# ir-kh.net
KiCad netlist of a schematic drawn in Altium Designer
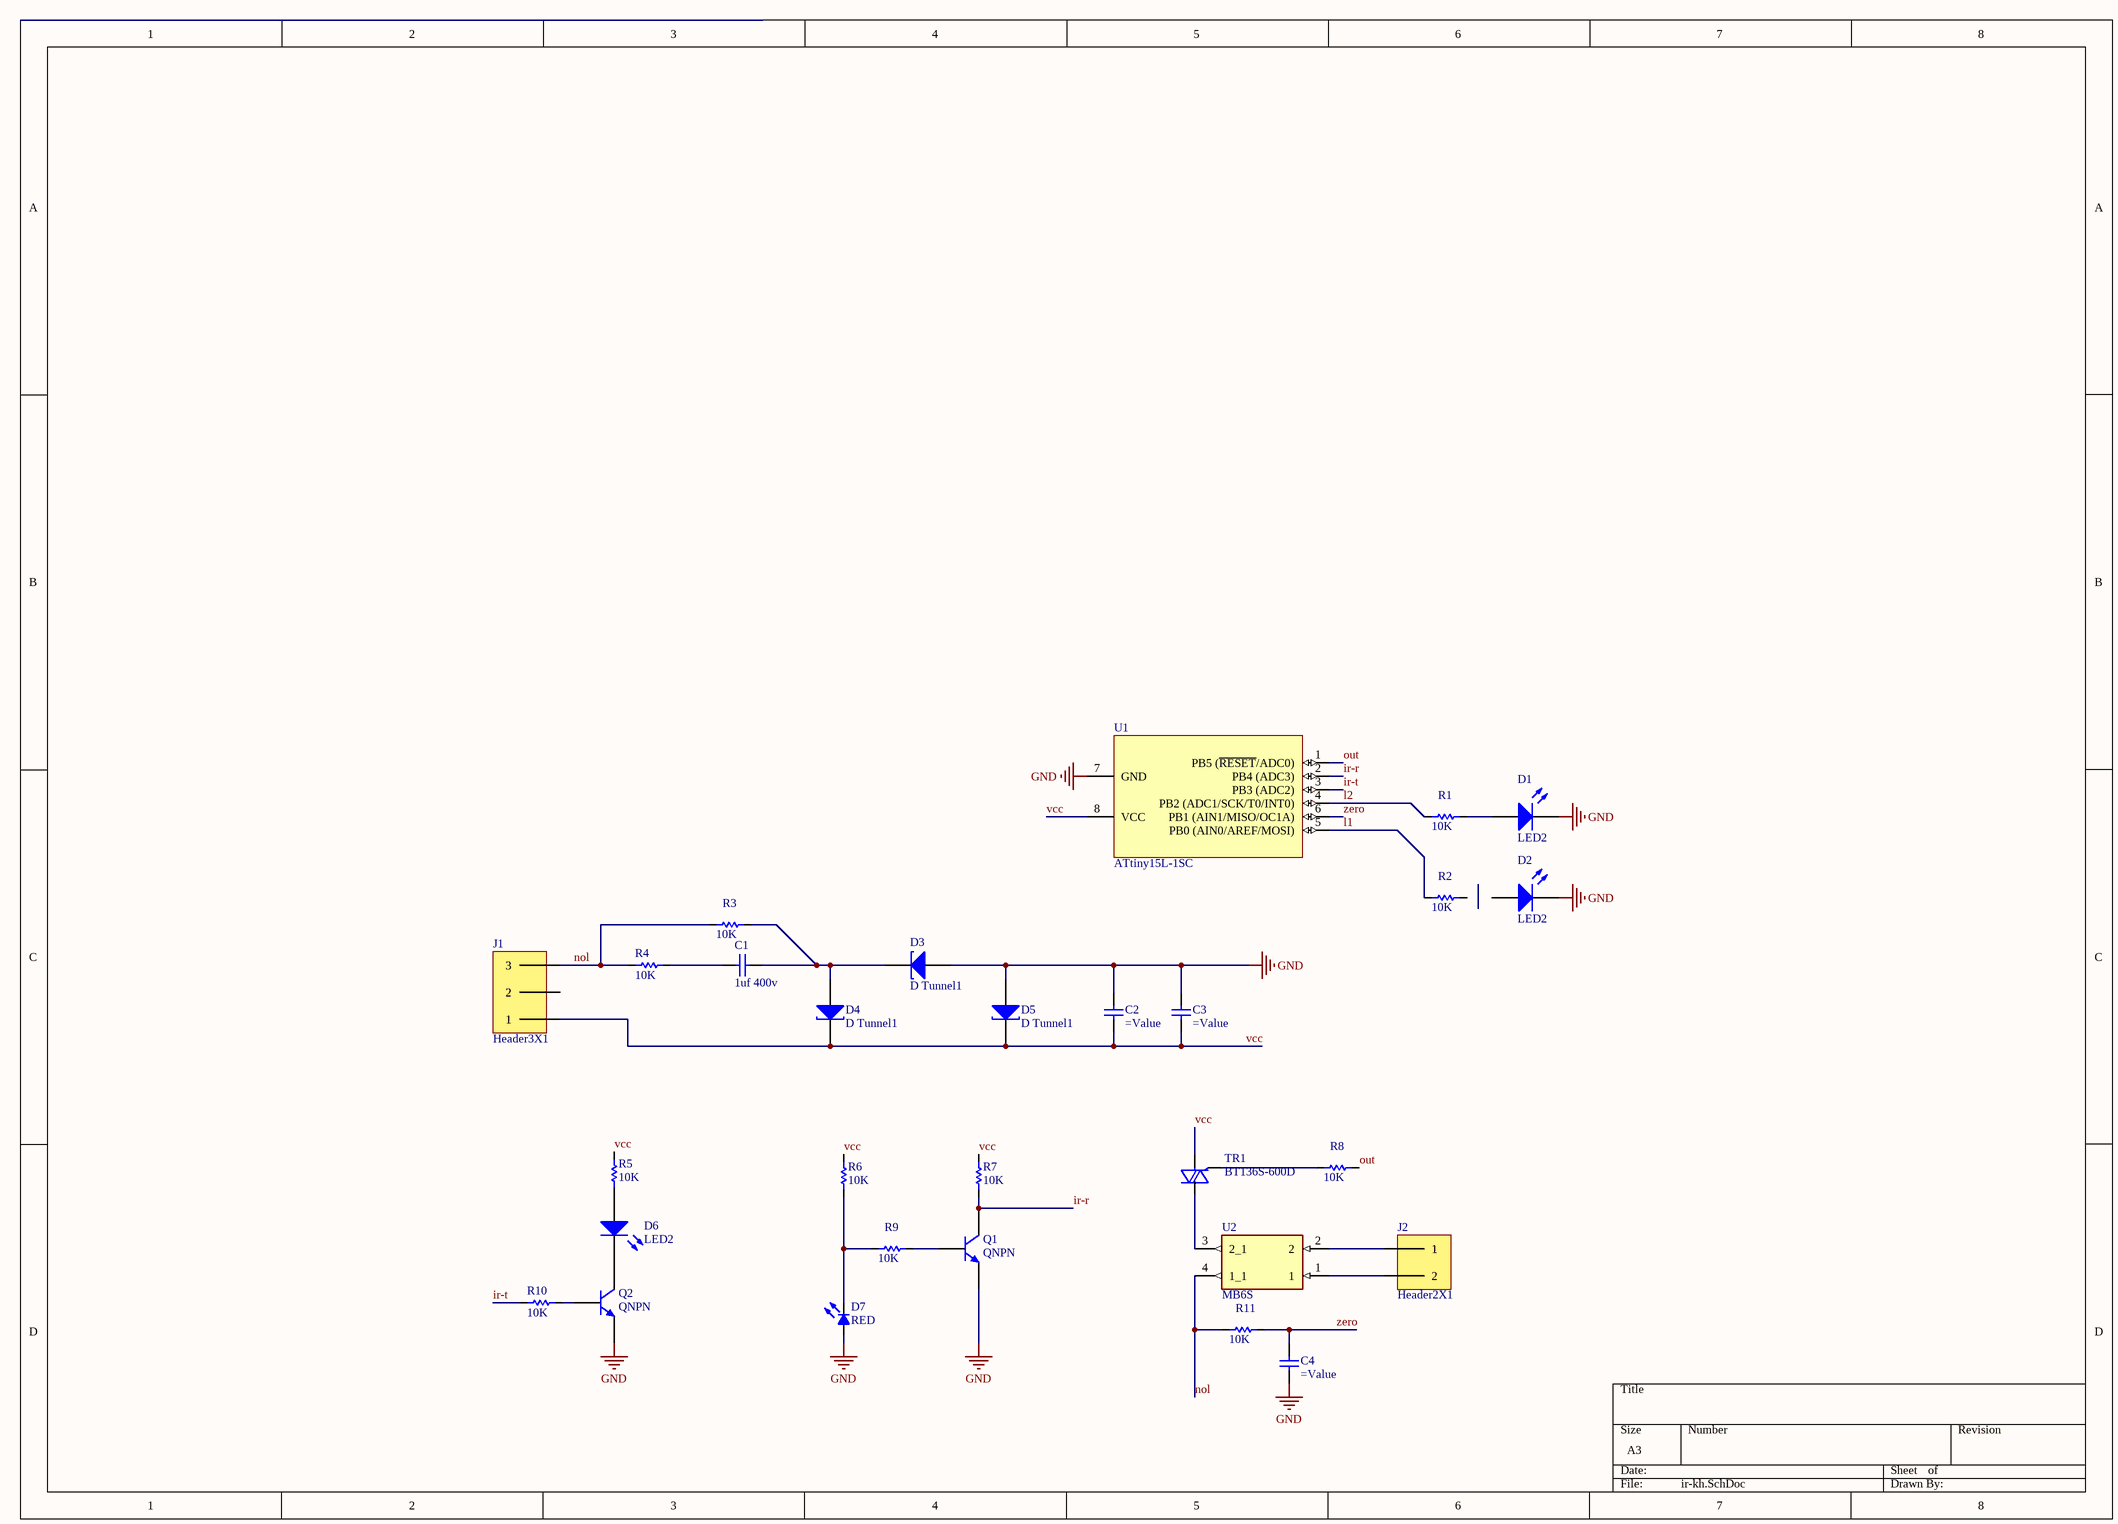
[diagram p0: ir-kh.SchDoc]

(export (version "E")
  (design (tool "Eeschema 10.0.6"))
  (components
    (comp (ref "C1")
      (value "1uf 400v")
      (footprint "1uf 400v")
      (description "Capacitor 24*9mm")
      (fields (field (name "DESIGNER") "Seyed Mohsen Ghasemain"))
      (libsource (lib "PicPars.com_usefully_Library") (part "1uf 400v"))
    )
    (comp (ref "C2")
      (value "~")
      (footprint "CAP 1206")
      (description "Capacitor")
      (libsource (lib "AltiumLib1") (part "Capacitor"))
    )
    (comp (ref "C3")
      (value "~")
      (footprint "CAP 1206")
      (description "Capacitor")
      (libsource (lib "AltiumLib1") (part "Capacitor"))
    )
    (comp (ref "C4")
      (value "~")
      (footprint "CAP 1206")
      (description "Capacitor")
      (libsource (lib "AltiumLib1") (part "Capacitor"))
    )
    (comp (ref "D1")
      (value "LED2")
      (footprint "3.2X1.6X1.1")
      (description "Typical RED, GREEN, YELLOW, AMBER GaAs LED")
      (fields (field (name "PUBLISHER") "Altium Limited"))
      (libsource (lib "Miscellaneous Devices") (part "LED2"))
    )
    (comp (ref "D2")
      (value "LED2")
      (footprint "3.2X1.6X1.1")
      (description "Typical RED, GREEN, YELLOW, AMBER GaAs LED")
      (fields (field (name "PUBLISHER") "Altium Limited"))
      (libsource (lib "Miscellaneous Devices") (part "LED2"))
    )
    (comp (ref "D3")
      (value "D Tunnel1")
      (footprint "3.2X1.6X1.1")
      (description "Tunnel Diode - RLC Model")
      (fields (field (name "PUBLISHER") "Altium Limited"))
      (libsource (lib "Miscellaneous Devices") (part "D Tunnel1"))
    )
    (comp (ref "D4")
      (value "D Tunnel1")
      (footprint "3.2X1.6X1.1")
      (description "Tunnel Diode - RLC Model")
      (fields (field (name "PUBLISHER") "Altium Limited"))
      (libsource (lib "Miscellaneous Devices") (part "D Tunnel1"))
    )
    (comp (ref "D5")
      (value "D Tunnel1")
      (footprint "3.2X1.6X1.1")
      (description "Tunnel Diode - RLC Model")
      (fields (field (name "PUBLISHER") "Altium Limited"))
      (libsource (lib "Miscellaneous Devices") (part "D Tunnel1"))
    )
    (comp (ref "D6")
      (value "LED2")
      (footprint "3.2X1.6X1.1")
      (description "Typical RED, GREEN, YELLOW, AMBER GaAs LED")
      (fields (field (name "PUBLISHER") "Altium Limited"))
      (libsource (lib "Miscellaneous Devices") (part "LED2"))
    )
    (comp (ref "D7")
      (value "MODEL")
      (footprint "LED-5mm")
      (description "Typical LED")
      (fields (field (name "COLOR") "RED"))
      (libsource (lib "AltiumLib1") (part "LED 5mm"))
    )
    (comp (ref "J1")
      (value "Header3X1")
      (footprint "HEADER 3X1")
      (libsource (lib "AltiumLib1") (part "Header3X1"))
    )
    (comp (ref "J2")
      (value "Header2X1")
      (footprint "Header 2X1")
      (libsource (lib "AltiumLib1") (part "Header2X1"))
    )
    (comp (ref "Q1")
      (value "QNPN")
      (footprint "SOT-23B_L")
      (description "NPN Bipolar Transistor")
      (fields (field (name "PUBLISHER") "Altium Limited"))
      (libsource (lib "Miscellaneous Devices") (part "QNPN"))
    )
    (comp (ref "Q2")
      (value "QNPN")
      (footprint "SOT-23B_L")
      (description "NPN Bipolar Transistor")
      (fields (field (name "PUBLISHER") "Altium Limited"))
      (libsource (lib "Miscellaneous Devices") (part "QNPN"))
    )
    (comp (ref "R1")
      (value "10K")
      (footprint "RES 1206 (3216X08L)")
      (description "Resistor")
      (fields (field (name "TOLERANCE") "5%") (field (name "POWER") "1/4 W"))
      (libsource (lib "AltiumLib1") (part "Resistor"))
    )
    (comp (ref "R2")
      (value "10K")
      (footprint "RES 1206 (3216X08L)")
      (description "Resistor")
      (fields (field (name "TOLERANCE") "5%") (field (name "POWER") "1/4 W"))
      (libsource (lib "AltiumLib1") (part "Resistor"))
    )
    (comp (ref "R3")
      (value "10K")
      (footprint "RES 1206 (3216X08L)")
      (description "Resistor")
      (fields (field (name "TOLERANCE") "5%") (field (name "POWER") "1/4 W"))
      (libsource (lib "AltiumLib1") (part "Resistor"))
    )
    (comp (ref "R4")
      (value "10K")
      (footprint "Res-(2/1)")
      (description "Resistor")
      (fields (field (name "TOLERANCE") "5%") (field (name "POWER") "1/4 W"))
      (libsource (lib "AltiumLib1") (part "Resistor"))
    )
    (comp (ref "R5")
      (value "10K")
      (footprint "RES 1206 (3216X08L)")
      (description "Resistor")
      (fields (field (name "TOLERANCE") "5%") (field (name "POWER") "1/4 W"))
      (libsource (lib "AltiumLib1") (part "Resistor"))
    )
    (comp (ref "R6")
      (value "10K")
      (footprint "RES 1206 (3216X08L)")
      (description "Resistor")
      (fields (field (name "TOLERANCE") "5%") (field (name "POWER") "1/4 W"))
      (libsource (lib "AltiumLib1") (part "Resistor"))
    )
    (comp (ref "R7")
      (value "10K")
      (footprint "RES 1206 (3216X08L)")
      (description "Resistor")
      (fields (field (name "TOLERANCE") "5%") (field (name "POWER") "1/4 W"))
      (libsource (lib "AltiumLib1") (part "Resistor"))
    )
    (comp (ref "R8")
      (value "10K")
      (footprint "RES 1206 (3216X08L)")
      (description "Resistor")
      (fields (field (name "TOLERANCE") "5%") (field (name "POWER") "1/4 W"))
      (libsource (lib "AltiumLib1") (part "Resistor"))
    )
    (comp (ref "R9")
      (value "10K")
      (footprint "RES 1206 (3216X08L)")
      (description "Resistor")
      (fields (field (name "TOLERANCE") "5%") (field (name "POWER") "1/4 W"))
      (libsource (lib "AltiumLib1") (part "Resistor"))
    )
    (comp (ref "R10")
      (value "10K")
      (footprint "RES 1206 (3216X08L)")
      (description "Resistor")
      (fields (field (name "TOLERANCE") "5%") (field (name "POWER") "1/4 W"))
      (libsource (lib "AltiumLib1") (part "Resistor"))
    )
    (comp (ref "R11")
      (value "10K")
      (footprint "RES 1206 (3216X08L)")
      (description "Resistor")
      (fields (field (name "TOLERANCE") "5%") (field (name "POWER") "1/4 W"))
      (libsource (lib "AltiumLib1") (part "Resistor"))
    )
    (comp (ref "TR1")
      (value "BT136S-600D")
      (footprint "SOT428")
      (description "TRIAC 600V 27A 3-Pin(2+Tab) DPAK")
      (fields (field (name "MF") "WeEn Semiconductor(Hong Kong)Co.,Limited"))
      (libsource (lib "BT136S-600D") (part "BT136S-600D"))
    )
    (comp (ref "U1")
      (value "ATtiny15L-1SC")
      (footprint "8S2_N")
      (description "8-Bit AVR Microcontroller with 1K Byte of Flash Memory")
      (fields (field (name "PUBLISHER") "Altium Limited"))
      (libsource (lib "Atmel Microcontroller 8-Bit AVR") (part "ATtiny15L-1SC"))
    )
    (comp (ref "U2")
      (value "MB6S")
      (footprint "SOIC245P670X270-4N")
      (description "Bridge Rectifier Single Phase Standard 600V Surface Mount 4-SOIC")
      (fields (field (name "MF") "ON Semiconductor") (field (name "DIGI-KEY_PART_NUMBER") "MB6SCT-ND"))
      (libsource (lib "MB6S") (part "MB6S"))
    )
  )
  (nets
    (net (code "1") (name "/ir-r") (class "Default")
      (node (ref "Q1") (pin "1") (pinfunction "C_1") (pintype "passive"))
      (node (ref "R7") (pin "2") (pinfunction "2_2") (pintype "passive"))
      (node (ref "U1") (pin "2") (pinfunction "PB4_(ADC3)_2") (pintype "bidirectional"))
    )
    (net (code "2") (name "/ir-t") (class "Default")
      (node (ref "R10") (pin "1") (pinfunction "1_1") (pintype "passive"))
      (node (ref "U1") (pin "3") (pinfunction "PB3_(ADC2)_3") (pintype "bidirectional"))
    )
    (net (code "3") (name "/l1") (class "Default")
      (node (ref "R2") (pin "1") (pinfunction "1_1") (pintype "passive"))
      (node (ref "U1") (pin "5") (pinfunction "PB0_(AIN0/AREF/MOSI)_5") (pintype "bidirectional"))
    )
    (net (code "4") (name "/l2") (class "Default")
      (node (ref "R1") (pin "1") (pinfunction "1_1") (pintype "passive"))
      (node (ref "U1") (pin "4") (pinfunction "PB2_(ADC1/SCK/T0/INT0)_4") (pintype "bidirectional"))
    )
    (net (code "5") (name "/nol") (class "Default")
      (node (ref "J1") (pin "3") (pinfunction "3_3") (pintype "passive"))
      (node (ref "R11") (pin "1") (pinfunction "1_1") (pintype "passive"))
      (node (ref "R3") (pin "1") (pinfunction "1_1") (pintype "passive"))
      (node (ref "R4") (pin "1") (pinfunction "1_1") (pintype "passive"))
      (node (ref "U2") (pin "4") (pinfunction "1_1_4") (pintype "output"))
    )
    (net (code "6") (name "/out") (class "Default")
      (node (ref "R8") (pin "2") (pinfunction "2_2") (pintype "passive"))
      (node (ref "U1") (pin "1") (pinfunction "PB5_(~{RESET}/ADC0)_1") (pintype "bidirectional"))
    )
    (net (code "7") (name "/vcc") (class "Default")
      (node (ref "C2") (pin "1") (pinfunction "+_1") (pintype "passive"))
      (node (ref "C3") (pin "1") (pinfunction "+_1") (pintype "passive"))
      (node (ref "D4") (pin "2") (pinfunction "K_2") (pintype "passive"))
      (node (ref "D5") (pin "2") (pinfunction "K_2") (pintype "passive"))
      (node (ref "J1") (pin "1") (pinfunction "1_1") (pintype "passive"))
      (node (ref "R5") (pin "2") (pinfunction "2_2") (pintype "passive"))
      (node (ref "R6") (pin "1") (pinfunction "1_1") (pintype "passive"))
      (node (ref "R7") (pin "1") (pinfunction "1_1") (pintype "passive"))
      (node (ref "TR1") (pin "1") (pinfunction "A1_1") (pintype "passive"))
      (node (ref "U1") (pin "8") (pinfunction "VCC_8") (pintype "power_in"))
    )
    (net (code "8") (name "/zero") (class "Default")
      (node (ref "C4") (pin "2") (pinfunction "-_2") (pintype "passive"))
      (node (ref "R11") (pin "2") (pinfunction "2_2") (pintype "passive"))
      (node (ref "U1") (pin "6") (pinfunction "PB1_(AIN1/MISO/OC1A)_6") (pintype "bidirectional"))
    )
    (net (code "9") (name "GND") (class "Default")
      (node (ref "C2") (pin "2") (pinfunction "-_2") (pintype "passive"))
      (node (ref "C3") (pin "2") (pinfunction "-_2") (pintype "passive"))
      (node (ref "C4") (pin "1") (pinfunction "+_1") (pintype "passive"))
      (node (ref "D1") (pin "2") (pinfunction "K_2") (pintype "passive"))
      (node (ref "D2") (pin "2") (pinfunction "K_2") (pintype "passive"))
      (node (ref "D3") (pin "1") (pinfunction "A_1") (pintype "passive"))
      (node (ref "D5") (pin "1") (pinfunction "A_1") (pintype "passive"))
      (node (ref "D7") (pin "1") (pinfunction "A_1") (pintype "passive"))
      (node (ref "Q1") (pin "3") (pinfunction "E_3") (pintype "passive"))
      (node (ref "Q2") (pin "3") (pinfunction "E_3") (pintype "passive"))
      (node (ref "U1") (pin "7") (pinfunction "GND_7") (pintype "power_in"))
    )
    (net (code "10") (name "Net-(C1-Pad1)") (class "Default")
      (node (ref "C1") (pin "1") (pinfunction "1_1") (pintype "passive"))
      (node (ref "R4") (pin "2") (pinfunction "2_2") (pintype "passive"))
    )
    (net (code "11") (name "Net-(D1-A)") (class "Default")
      (node (ref "D1") (pin "1") (pinfunction "A_1") (pintype "passive"))
      (node (ref "R1") (pin "2") (pinfunction "2_2") (pintype "passive"))
    )
    (net (code "12") (name "Net-(D3-K)") (class "Default")
      (node (ref "C1") (pin "2") (pinfunction "2_2") (pintype "passive"))
      (node (ref "D3") (pin "2") (pinfunction "K_2") (pintype "passive"))
      (node (ref "D4") (pin "1") (pinfunction "A_1") (pintype "passive"))
      (node (ref "R3") (pin "2") (pinfunction "2_2") (pintype "passive"))
    )
    (net (code "13") (name "Net-(D6-A)") (class "Default")
      (node (ref "D6") (pin "1") (pinfunction "A_1") (pintype "passive"))
      (node (ref "R5") (pin "1") (pinfunction "1_1") (pintype "passive"))
    )
    (net (code "14") (name "Net-(D6-K)") (class "Default")
      (node (ref "D6") (pin "2") (pinfunction "K_2") (pintype "passive"))
      (node (ref "Q2") (pin "1") (pinfunction "C_1") (pintype "passive"))
    )
    (net (code "15") (name "Net-(D7-K)") (class "Default")
      (node (ref "D7") (pin "2") (pinfunction "K_2") (pintype "passive"))
      (node (ref "R6") (pin "2") (pinfunction "2_2") (pintype "passive"))
      (node (ref "R9") (pin "1") (pinfunction "1_1") (pintype "passive"))
    )
    (net (code "16") (name "Net-(J2-Pad1)") (class "Default")
      (node (ref "J2") (pin "1") (pinfunction "1_1") (pintype "passive"))
      (node (ref "U2") (pin "2") (pinfunction "2_2") (pintype "input"))
    )
    (net (code "17") (name "Net-(J2-Pad2)") (class "Default")
      (node (ref "J2") (pin "2") (pinfunction "2_2") (pintype "passive"))
      (node (ref "U2") (pin "1") (pinfunction "1_1") (pintype "input"))
    )
    (net (code "18") (name "Net-(Q1-B)") (class "Default")
      (node (ref "Q1") (pin "2") (pinfunction "B_2") (pintype "passive"))
      (node (ref "R9") (pin "2") (pinfunction "2_2") (pintype "passive"))
    )
    (net (code "19") (name "Net-(Q2-B)") (class "Default")
      (node (ref "Q2") (pin "2") (pinfunction "B_2") (pintype "passive"))
      (node (ref "R10") (pin "2") (pinfunction "2_2") (pintype "passive"))
    )
    (net (code "20") (name "Net-(TR1-A2)") (class "Default")
      (node (ref "TR1") (pin "MB") (pinfunction "A2_MB") (pintype "passive"))
      (node (ref "U2") (pin "3") (pinfunction "2_1_3") (pintype "output"))
    )
    (net (code "21") (name "Net-(TR1-G)") (class "Default")
      (node (ref "R8") (pin "1") (pinfunction "1_1") (pintype "passive"))
      (node (ref "TR1") (pin "3") (pinfunction "G_3") (pintype "passive"))
    )
    (net (code "22") (name "unconnected-(D2-A-Pad1)") (class "Default")
      (node (ref "D2") (pin "1") (pinfunction "A_1") (pintype "passive"))
    )
    (net (code "23") (name "unconnected-(J1-Pad2)") (class "Default")
      (node (ref "J1") (pin "2") (pinfunction "2_2") (pintype "passive"))
    )
    (net (code "24") (name "unconnected-(R2-Pad2)") (class "Default")
      (node (ref "R2") (pin "2") (pinfunction "2_2") (pintype "passive"))
    )
  )
)
